# lipoWing.net
KiCad netlist of a schematic drawn in EAGLE
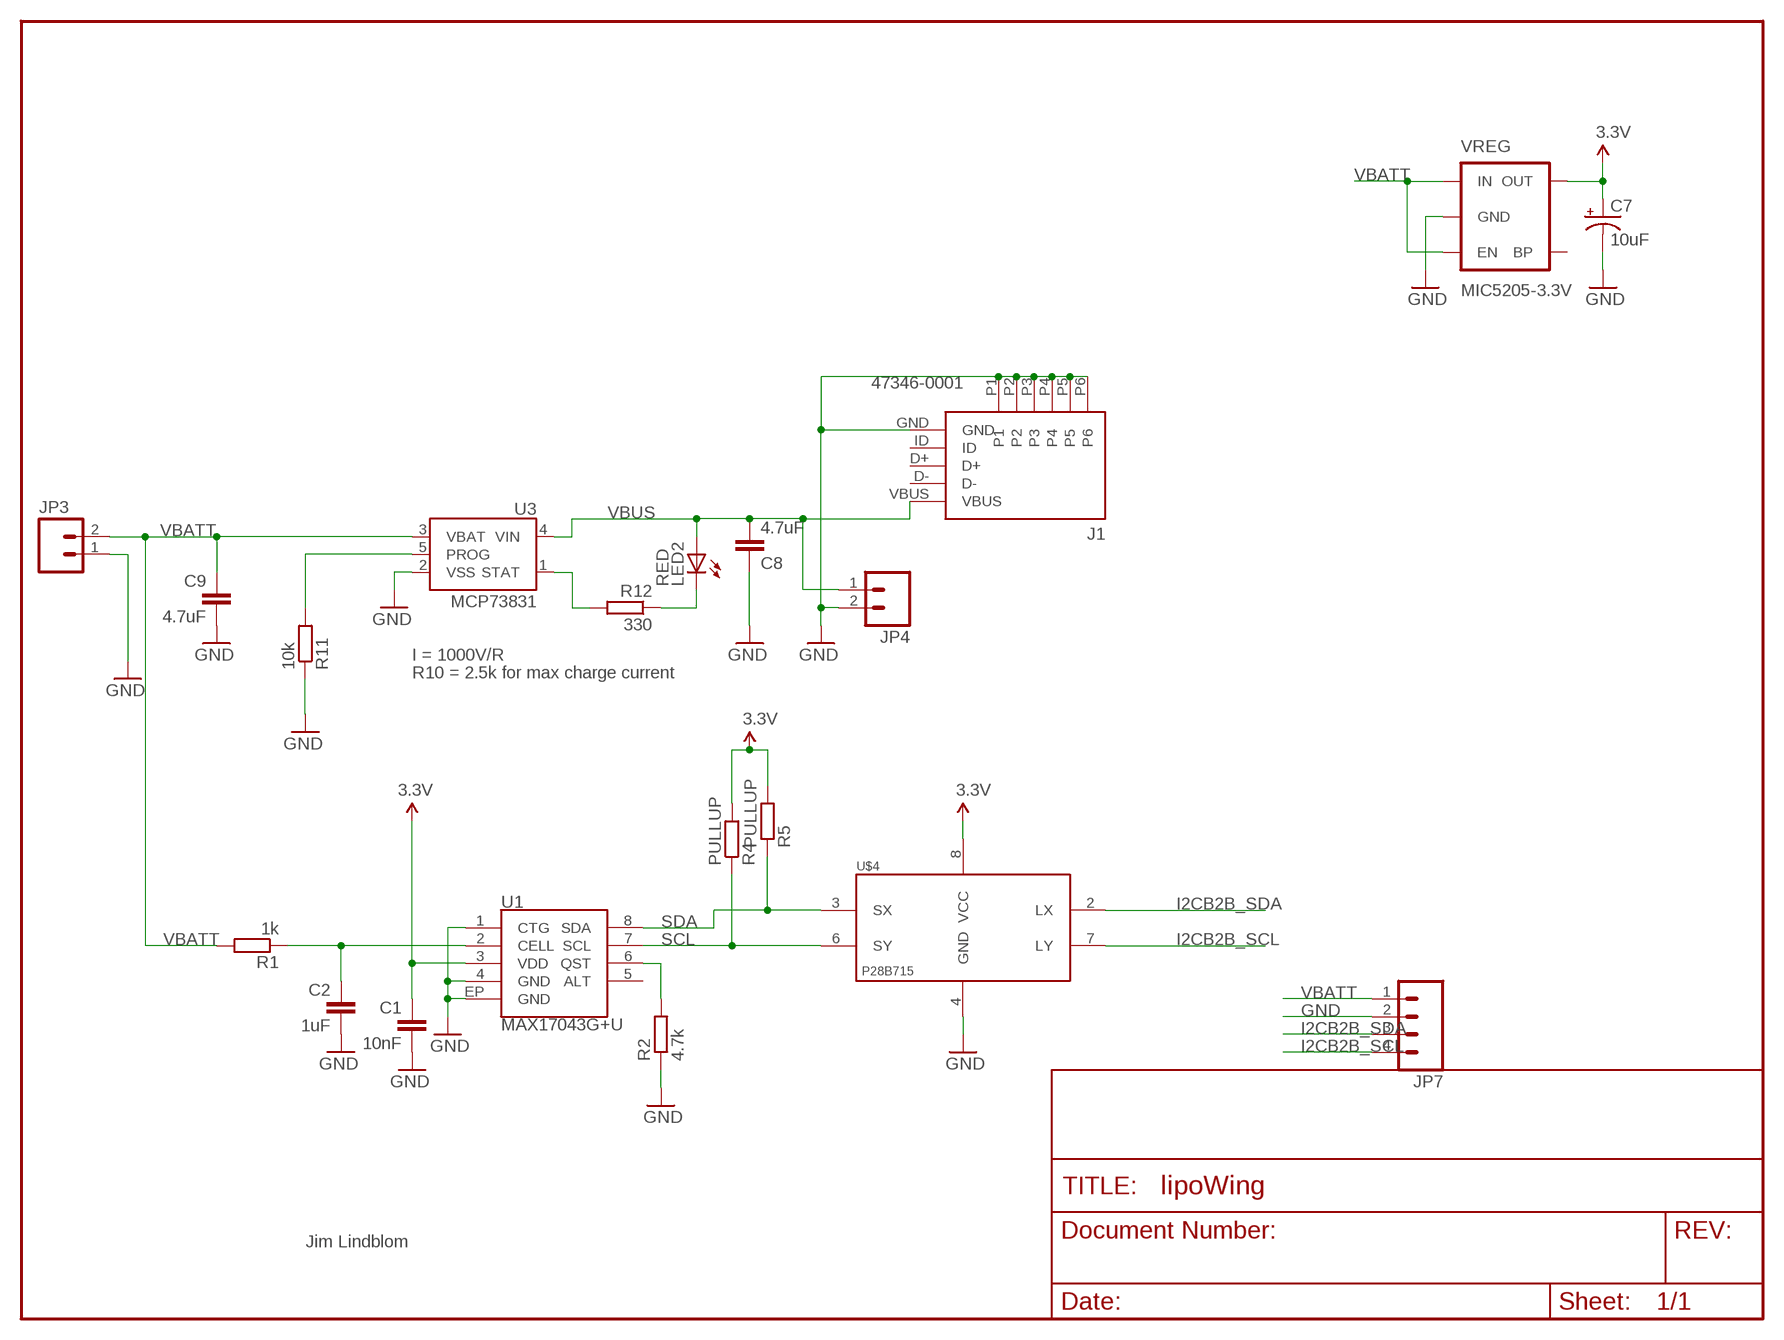
[diagram p0: schematic, sheet 1]

(export (version "E")
  (design (tool "Eeschema 10.0.6"))
  (components
    (comp (ref "C1")
      (value "10nF")
      (footprint "eagle-import:C0603")
      (libsource (lib "eagle-import") (part "C0603"))
    )
    (comp (ref "C2")
      (value "1uF")
      (footprint "eagle-import:C0603")
      (libsource (lib "eagle-import") (part "C0603"))
    )
    (comp (ref "C7")
      (value "10uF")
      (footprint "eagle-import:EIA3216")
      (libsource (lib "eagle-import") (part "CAP_POL1206"))
    )
    (comp (ref "C8")
      (value "4.7uF")
      (footprint "eagle-import:C0603")
      (libsource (lib "eagle-import") (part "C0603"))
    )
    (comp (ref "C9")
      (value "4.7uF")
      (footprint "eagle-import:C0603")
      (libsource (lib "eagle-import") (part "C0603"))
    )
    (comp (ref "J1")
      (value "47346-0001")
      (footprint "eagle-import:MICRO_USB")
      (fields (field (name "PARTNO") "AS-ITM-00021"))
      (libsource (lib "eagle-import") (part "MICRO-USB"))
    )
    (comp (ref "JP3")
      (value "M021X02_NO_SILK")
      (footprint "eagle-import:1X02_NO_SILK")
      (libsource (lib "eagle-import") (part "M021X02_NO_SILK"))
    )
    (comp (ref "JP4")
      (value "M021X02_NO_SILK")
      (footprint "eagle-import:1X02_NO_SILK")
      (libsource (lib "eagle-import") (part "M021X02_NO_SILK"))
    )
    (comp (ref "JP7")
      (value "M04JST")
      (footprint "eagle-import:1X04-1.5MM_JST")
      (libsource (lib "eagle-import") (part "M04JST"))
    )
    (comp (ref "LED2")
      (value "RED")
      (footprint "eagle-import:LED-0603")
      (libsource (lib "eagle-import") (part "LED0603"))
    )
    (comp (ref "R1")
      (value "1k")
      (footprint "eagle-import:R0603")
      (libsource (lib "eagle-import") (part "R0603"))
    )
    (comp (ref "R2")
      (value "4.7k")
      (footprint "eagle-import:R0603")
      (libsource (lib "eagle-import") (part "R0603"))
    )
    (comp (ref "R4")
      (value "PULLUP")
      (footprint "eagle-import:R0603")
      (libsource (lib "eagle-import") (part "R0603"))
    )
    (comp (ref "R5")
      (value "PULLUP")
      (footprint "eagle-import:R0603")
      (libsource (lib "eagle-import") (part "R0603"))
    )
    (comp (ref "R11")
      (value "10k")
      (footprint "eagle-import:R0603")
      (libsource (lib "eagle-import") (part "R0603"))
    )
    (comp (ref "R12")
      (value "330")
      (footprint "eagle-import:R0603")
      (libsource (lib "eagle-import") (part "R0603"))
    )
    (comp (ref "U$4")
      (value "P82B715")
      (footprint "eagle-import:SO8")
      (libsource (lib "eagle-import") (part "P82B715"))
    )
    (comp (ref "U1")
      (value "MAX17043G+U")
      (footprint "eagle-import:TDFN-8")
      (libsource (lib "eagle-import") (part "MAX1704X"))
    )
    (comp (ref "U3")
      (value "MCP73831")
      (footprint "eagle-import:SOT23-5")
      (libsource (lib "eagle-import") (part "MCP73831"))
    )
    (comp (ref "VREG")
      (value "MIC5205-3.3V")
      (footprint "eagle-import:SOT23-5")
      (libsource (lib "eagle-import") (part "V_REG_LDOSMD"))
    )
  )
  (nets
    (net (code "1") (name "/I2CB2B_SCL") (class "Default")
      (node (ref "JP7") (pin "4") (pinfunction "4_4") (pintype "passive"))
      (node (ref "U$4") (pin "7") (pinfunction "LY_7") (pintype "bidirectional"))
    )
    (net (code "2") (name "/I2CB2B_SDA") (class "Default")
      (node (ref "JP7") (pin "3") (pinfunction "3_3") (pintype "passive"))
      (node (ref "U$4") (pin "2") (pinfunction "LX_2") (pintype "bidirectional"))
    )
    (net (code "3") (name "/SCL") (class "Default")
      (node (ref "R4") (pin "1") (pinfunction "1_1") (pintype "passive"))
      (node (ref "U$4") (pin "6") (pinfunction "SY_6") (pintype "bidirectional"))
      (node (ref "U1") (pin "7") (pinfunction "SCL_7") (pintype "bidirectional"))
    )
    (net (code "4") (name "/SDA") (class "Default")
      (node (ref "R5") (pin "1") (pinfunction "1_1") (pintype "passive"))
      (node (ref "U$4") (pin "3") (pinfunction "SX_3") (pintype "bidirectional"))
      (node (ref "U1") (pin "8") (pinfunction "SDA_8") (pintype "bidirectional"))
    )
    (net (code "5") (name "/VBATT") (class "Default")
      (node (ref "C9") (pin "1") (pinfunction "1_1") (pintype "passive"))
      (node (ref "JP3") (pin "2") (pinfunction "2_2") (pintype "passive"))
      (node (ref "JP7") (pin "1") (pinfunction "1_1") (pintype "passive"))
      (node (ref "R1") (pin "2") (pinfunction "2_2") (pintype "passive"))
      (node (ref "U3") (pin "3") (pinfunction "VBAT_3") (pintype "power_in"))
      (node (ref "VREG") (pin "1") (pinfunction "IN_1") (pintype "input"))
      (node (ref "VREG") (pin "3") (pinfunction "EN_3") (pintype "input"))
    )
    (net (code "6") (name "/VBUS") (class "Default")
      (node (ref "C8") (pin "2") (pinfunction "2_2") (pintype "passive"))
      (node (ref "J1") (pin "VBUS") (pinfunction "VBUS_VBUS") (pintype "bidirectional"))
      (node (ref "JP4") (pin "1") (pinfunction "1_1") (pintype "passive"))
      (node (ref "LED2") (pin "A") (pinfunction "A_A") (pintype "passive"))
      (node (ref "U3") (pin "4") (pinfunction "VIN_4") (pintype "power_in"))
    )
    (net (code "7") (name "3.3V") (class "Default")
      (node (ref "C1") (pin "1") (pinfunction "1_1") (pintype "passive"))
      (node (ref "C7") (pin "A") (pinfunction "+_A") (pintype "passive"))
      (node (ref "R4") (pin "2") (pinfunction "2_2") (pintype "passive"))
      (node (ref "R5") (pin "2") (pinfunction "2_2") (pintype "passive"))
      (node (ref "U$4") (pin "8") (pinfunction "VCC_8") (pintype "bidirectional"))
      (node (ref "U1") (pin "3") (pinfunction "VDD_3") (pintype "bidirectional"))
      (node (ref "VREG") (pin "5") (pinfunction "OUT_5") (pintype "passive"))
    )
    (net (code "8") (name "GND") (class "Default")
      (node (ref "C1") (pin "2") (pinfunction "2_2") (pintype "passive"))
      (node (ref "C2") (pin "2") (pinfunction "2_2") (pintype "passive"))
      (node (ref "C7") (pin "C") (pinfunction "-_C") (pintype "passive"))
      (node (ref "C8") (pin "1") (pinfunction "1_1") (pintype "passive"))
      (node (ref "C9") (pin "2") (pinfunction "2_2") (pintype "passive"))
      (node (ref "J1") (pin "GND") (pinfunction "GND_GND") (pintype "bidirectional"))
      (node (ref "J1") (pin "P1") (pinfunction "P1_P1") (pintype "bidirectional"))
      (node (ref "J1") (pin "P2") (pinfunction "P2_P2") (pintype "bidirectional"))
      (node (ref "J1") (pin "P3") (pinfunction "P3_P3") (pintype "bidirectional"))
      (node (ref "J1") (pin "P4") (pinfunction "P4_P4") (pintype "bidirectional"))
      (node (ref "J1") (pin "P5") (pinfunction "P5_P5") (pintype "bidirectional"))
      (node (ref "J1") (pin "P6") (pinfunction "P6_P6") (pintype "bidirectional"))
      (node (ref "JP3") (pin "1") (pinfunction "1_1") (pintype "passive"))
      (node (ref "JP4") (pin "2") (pinfunction "2_2") (pintype "passive"))
      (node (ref "JP7") (pin "2") (pinfunction "2_2") (pintype "passive"))
      (node (ref "R11") (pin "1") (pinfunction "1_1") (pintype "passive"))
      (node (ref "R2") (pin "1") (pinfunction "1_1") (pintype "passive"))
      (node (ref "U$4") (pin "4") (pinfunction "GND_4") (pintype "bidirectional"))
      (node (ref "U1") (pin "1") (pinfunction "CTG_1") (pintype "bidirectional"))
      (node (ref "U1") (pin "4") (pinfunction "GND_4") (pintype "bidirectional"))
      (node (ref "U1") (pin "EP") (pinfunction "GND_EP") (pintype "bidirectional"))
      (node (ref "U3") (pin "2") (pinfunction "VSS_2") (pintype "power_in"))
      (node (ref "VREG") (pin "2") (pinfunction "GND_2") (pintype "input"))
    )
    (net (code "9") (name "Net-(LED2-PadC)") (class "Default")
      (node (ref "LED2") (pin "C") (pinfunction "C_C") (pintype "passive"))
      (node (ref "R12") (pin "1") (pinfunction "1_1") (pintype "passive"))
    )
    (net (code "10") (name "Net-(U1-CELL)") (class "Default")
      (node (ref "C2") (pin "1") (pinfunction "1_1") (pintype "passive"))
      (node (ref "R1") (pin "1") (pinfunction "1_1") (pintype "passive"))
      (node (ref "U1") (pin "2") (pinfunction "CELL_2") (pintype "bidirectional"))
    )
    (net (code "11") (name "Net-(U1-QST)") (class "Default")
      (node (ref "R2") (pin "2") (pinfunction "2_2") (pintype "passive"))
      (node (ref "U1") (pin "6") (pinfunction "QST_6") (pintype "bidirectional"))
    )
    (net (code "12") (name "Net-(U3-PROG)") (class "Default")
      (node (ref "R11") (pin "2") (pinfunction "2_2") (pintype "passive"))
      (node (ref "U3") (pin "5") (pinfunction "PROG_5") (pintype "input"))
    )
    (net (code "13") (name "Net-(U3-STAT)") (class "Default")
      (node (ref "R12") (pin "2") (pinfunction "2_2") (pintype "passive"))
      (node (ref "U3") (pin "1") (pinfunction "STAT_1") (pintype "output"))
    )
    (net (code "14") (name "unconnected-(J1-PadD+)") (class "Default")
      (node (ref "J1") (pin "D+") (pinfunction "D+_D+") (pintype "bidirectional"))
    )
    (net (code "15") (name "unconnected-(J1-PadD-)") (class "Default")
      (node (ref "J1") (pin "D-") (pinfunction "D-_D-") (pintype "bidirectional"))
    )
    (net (code "16") (name "unconnected-(J1-PadID)") (class "Default")
      (node (ref "J1") (pin "ID") (pinfunction "ID_ID") (pintype "bidirectional"))
    )
    (net (code "17") (name "unconnected-(U1-ALT-Pad5)") (class "Default")
      (node (ref "U1") (pin "5") (pinfunction "ALT_5") (pintype "bidirectional"))
    )
    (net (code "18") (name "unconnected-(VREG-BP-Pad4)") (class "Default")
      (node (ref "VREG") (pin "4") (pinfunction "BP_4") (pintype "input"))
    )
  )
)
